# generic_micro_1.net
KiCad netlist of a schematic drawn in EAGLE
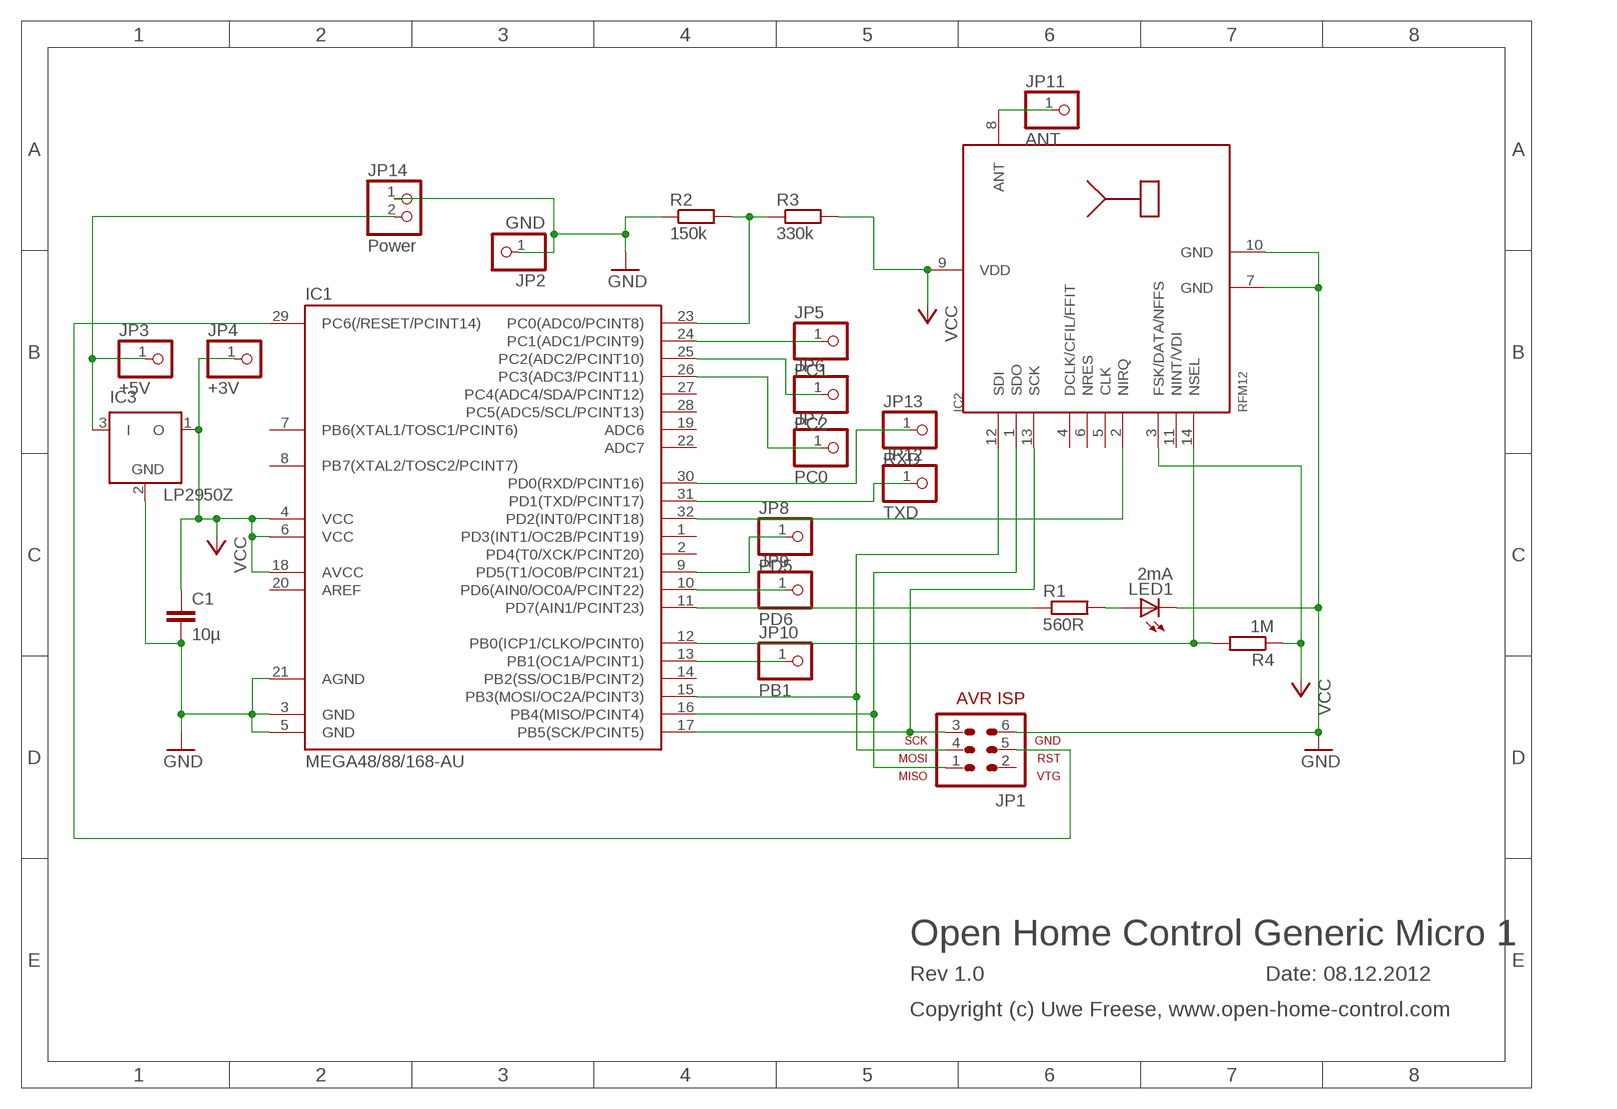
[diagram p0: schematic, sheet 1]

(export (version "E")
  (design (tool "Eeschema 10.0.6"))
  (components
    (comp (ref "C1")
      (value "10µ")
      (footprint "eagle-import:C0805")
      (libsource (lib "eagle-import") (part "C-EUC0805"))
    )
    (comp (ref "IC1")
      (value "MEGA48/88/168-AU")
      (footprint "eagle-import:TQFP32-08")
      (libsource (lib "eagle-import") (part "MEGA48/88/168-AU"))
    )
    (comp (ref "IC2")
      (value "RFM12")
      (footprint "eagle-import:RFM")
      (libsource (lib "eagle-import") (part "RFM12"))
    )
    (comp (ref "IC3")
      (value "LP2950Z")
      (footprint "eagle-import:TO92")
      (libsource (lib "eagle-import") (part "LP2950Z"))
    )
    (comp (ref "JP1")
      (value "AVR-ISP-6")
      (footprint "eagle-import:AVR-ISP-6")
      (libsource (lib "eagle-import") (part "AVR-ISP-6"))
    )
    (comp (ref "JP2")
      (value "GND")
      (footprint "eagle-import:1X01")
      (libsource (lib "eagle-import") (part "PINHD-1X1"))
    )
    (comp (ref "JP3")
      (value "+5V")
      (footprint "eagle-import:1X01")
      (libsource (lib "eagle-import") (part "PINHD-1X1"))
    )
    (comp (ref "JP4")
      (value "+3V")
      (footprint "eagle-import:1X01")
      (libsource (lib "eagle-import") (part "PINHD-1X1"))
    )
    (comp (ref "JP5")
      (value "PC1")
      (footprint "eagle-import:1X01")
      (libsource (lib "eagle-import") (part "PINHD-1X1"))
    )
    (comp (ref "JP6")
      (value "PC2")
      (footprint "eagle-import:1X01")
      (libsource (lib "eagle-import") (part "PINHD-1X1"))
    )
    (comp (ref "JP7")
      (value "PC0")
      (footprint "eagle-import:1X01")
      (libsource (lib "eagle-import") (part "PINHD-1X1"))
    )
    (comp (ref "JP8")
      (value "PD5")
      (footprint "eagle-import:1X01")
      (libsource (lib "eagle-import") (part "PINHD-1X1"))
    )
    (comp (ref "JP9")
      (value "PD6")
      (footprint "eagle-import:1X01")
      (libsource (lib "eagle-import") (part "PINHD-1X1"))
    )
    (comp (ref "JP10")
      (value "PB1")
      (footprint "eagle-import:1X01")
      (libsource (lib "eagle-import") (part "PINHD-1X1"))
    )
    (comp (ref "JP11")
      (value "ANT")
      (footprint "eagle-import:1X01")
      (libsource (lib "eagle-import") (part "PINHD-1X1"))
    )
    (comp (ref "JP12")
      (value "TXD")
      (footprint "eagle-import:1X01")
      (libsource (lib "eagle-import") (part "PINHD-1X1"))
    )
    (comp (ref "JP13")
      (value "RXD")
      (footprint "eagle-import:1X01")
      (libsource (lib "eagle-import") (part "PINHD-1X1"))
    )
    (comp (ref "JP14")
      (value "Power")
      (footprint "eagle-import:1X02")
      (libsource (lib "eagle-import") (part "PINHD-1X2"))
    )
    (comp (ref "LED1")
      (value "2mA")
      (footprint "eagle-import:LED3MM")
      (libsource (lib "eagle-import") (part "LED3MM"))
    )
    (comp (ref "R1")
      (value "560R")
      (footprint "eagle-import:R0603")
      (libsource (lib "eagle-import") (part "R-EU_R0603"))
    )
    (comp (ref "R2")
      (value "150k")
      (footprint "eagle-import:R0603")
      (libsource (lib "eagle-import") (part "R-EU_R0603"))
    )
    (comp (ref "R3")
      (value "330k")
      (footprint "eagle-import:R0603")
      (libsource (lib "eagle-import") (part "R-EU_R0603"))
    )
    (comp (ref "R4")
      (value "1M")
      (footprint "eagle-import:R0603")
      (libsource (lib "eagle-import") (part "R-EU_R0603"))
    )
  )
  (nets
    (net (code "1") (name "GND") (class "Default")
      (node (ref "C1") (pin "2") (pinfunction "2_2") (pintype "passive"))
      (node (ref "IC1") (pin "21") (pinfunction "AGND_21") (pintype "power_in"))
      (node (ref "IC1") (pin "3") (pinfunction "GND_3") (pintype "power_in"))
      (node (ref "IC1") (pin "5") (pinfunction "GND_5") (pintype "power_in"))
      (node (ref "IC2") (pin "10") (pinfunction "GND_10") (pintype "power_in"))
      (node (ref "IC2") (pin "7") (pinfunction "GND_7") (pintype "power_in"))
      (node (ref "IC3") (pin "2") (pinfunction "GND_2") (pintype "power_in"))
      (node (ref "JP1") (pin "6") (pinfunction "6_6") (pintype "passive"))
      (node (ref "JP14") (pin "1") (pinfunction "1_1") (pintype "passive"))
      (node (ref "JP2") (pin "1") (pinfunction "1_1") (pintype "passive"))
      (node (ref "LED1") (pin "K") (pinfunction "C_K") (pintype "passive"))
      (node (ref "R2") (pin "1") (pinfunction "1_1") (pintype "passive"))
    )
    (net (code "2") (name "Net-(IC1-PB0(ICP1{slash}CLKO{slash}PCINT0))") (class "Default")
      (node (ref "IC1") (pin "12") (pinfunction "PB0(ICP1/CLKO/PCINT0)_12") (pintype "bidirectional"))
      (node (ref "IC2") (pin "14") (pinfunction "NSEL_14") (pintype "bidirectional"))
      (node (ref "R4") (pin "2") (pinfunction "2_2") (pintype "passive"))
    )
    (net (code "3") (name "Net-(IC1-PB1(OC1A{slash}PCINT1))") (class "Default")
      (node (ref "IC1") (pin "13") (pinfunction "PB1(OC1A/PCINT1)_13") (pintype "bidirectional"))
      (node (ref "JP10") (pin "1") (pinfunction "1_1") (pintype "passive"))
    )
    (net (code "4") (name "Net-(IC1-PB3(MOSI{slash}OC2A{slash}PCINT3))") (class "Default")
      (node (ref "IC1") (pin "15") (pinfunction "PB3(MOSI/OC2A/PCINT3)_15") (pintype "bidirectional"))
      (node (ref "IC2") (pin "12") (pinfunction "SDI_12") (pintype "bidirectional"))
      (node (ref "JP1") (pin "4") (pinfunction "4_4") (pintype "passive"))
    )
    (net (code "5") (name "Net-(IC1-PB4(MISO{slash}PCINT4))") (class "Default")
      (node (ref "IC1") (pin "16") (pinfunction "PB4(MISO/PCINT4)_16") (pintype "bidirectional"))
      (node (ref "IC2") (pin "1") (pinfunction "SDO_1") (pintype "bidirectional"))
      (node (ref "JP1") (pin "1") (pinfunction "1_1") (pintype "passive"))
    )
    (net (code "6") (name "Net-(IC1-PB5(SCK{slash}PCINT5))") (class "Default")
      (node (ref "IC1") (pin "17") (pinfunction "PB5(SCK/PCINT5)_17") (pintype "bidirectional"))
      (node (ref "IC2") (pin "13") (pinfunction "SCK_13") (pintype "bidirectional"))
      (node (ref "JP1") (pin "3") (pinfunction "3_3") (pintype "passive"))
    )
    (net (code "7") (name "Net-(IC1-PC0(ADC0{slash}PCINT8))") (class "Default")
      (node (ref "IC1") (pin "23") (pinfunction "PC0(ADC0/PCINT8)_23") (pintype "bidirectional"))
      (node (ref "R2") (pin "2") (pinfunction "2_2") (pintype "passive"))
      (node (ref "R3") (pin "1") (pinfunction "1_1") (pintype "passive"))
    )
    (net (code "8") (name "Net-(IC1-PC1(ADC1{slash}PCINT9))") (class "Default")
      (node (ref "IC1") (pin "24") (pinfunction "PC1(ADC1/PCINT9)_24") (pintype "bidirectional"))
      (node (ref "JP5") (pin "1") (pinfunction "1_1") (pintype "passive"))
    )
    (net (code "9") (name "Net-(IC1-PC2(ADC2{slash}PCINT10))") (class "Default")
      (node (ref "IC1") (pin "25") (pinfunction "PC2(ADC2/PCINT10)_25") (pintype "bidirectional"))
      (node (ref "JP6") (pin "1") (pinfunction "1_1") (pintype "passive"))
    )
    (net (code "10") (name "Net-(IC1-PC3(ADC3{slash}PCINT11))") (class "Default")
      (node (ref "IC1") (pin "26") (pinfunction "PC3(ADC3/PCINT11)_26") (pintype "bidirectional"))
      (node (ref "JP7") (pin "1") (pinfunction "1_1") (pintype "passive"))
    )
    (net (code "11") (name "Net-(IC1-PC6({slash}RESET{slash}PCINT14))") (class "Default")
      (node (ref "IC1") (pin "29") (pinfunction "PC6(/RESET/PCINT14)_29") (pintype "bidirectional"))
      (node (ref "JP1") (pin "5") (pinfunction "5_5") (pintype "passive"))
    )
    (net (code "12") (name "Net-(IC1-PD0(RXD{slash}PCINT16))") (class "Default")
      (node (ref "IC1") (pin "30") (pinfunction "PD0(RXD/PCINT16)_30") (pintype "bidirectional"))
      (node (ref "JP13") (pin "1") (pinfunction "1_1") (pintype "passive"))
    )
    (net (code "13") (name "Net-(IC1-PD1(TXD{slash}PCINT17))") (class "Default")
      (node (ref "IC1") (pin "31") (pinfunction "PD1(TXD/PCINT17)_31") (pintype "bidirectional"))
      (node (ref "JP12") (pin "1") (pinfunction "1_1") (pintype "passive"))
    )
    (net (code "14") (name "Net-(IC1-PD2(INT0{slash}PCINT18))") (class "Default")
      (node (ref "IC1") (pin "32") (pinfunction "PD2(INT0/PCINT18)_32") (pintype "bidirectional"))
      (node (ref "IC2") (pin "2") (pinfunction "NIRQ_2") (pintype "bidirectional"))
    )
    (net (code "15") (name "Net-(IC1-PD5(T1{slash}OC0B{slash}PCINT21))") (class "Default")
      (node (ref "IC1") (pin "9") (pinfunction "PD5(T1/OC0B/PCINT21)_9") (pintype "bidirectional"))
      (node (ref "JP8") (pin "1") (pinfunction "1_1") (pintype "passive"))
    )
    (net (code "16") (name "Net-(IC1-PD6(AIN0{slash}OC0A{slash}PCINT22))") (class "Default")
      (node (ref "IC1") (pin "10") (pinfunction "PD6(AIN0/OC0A/PCINT22)_10") (pintype "bidirectional"))
      (node (ref "JP9") (pin "1") (pinfunction "1_1") (pintype "passive"))
    )
    (net (code "17") (name "Net-(IC1-PD7(AIN1{slash}PCINT23))") (class "Default")
      (node (ref "IC1") (pin "11") (pinfunction "PD7(AIN1/PCINT23)_11") (pintype "bidirectional"))
      (node (ref "R1") (pin "1") (pinfunction "1_1") (pintype "passive"))
    )
    (net (code "18") (name "Net-(IC2-ANT)") (class "Default")
      (node (ref "IC2") (pin "8") (pinfunction "ANT_8") (pintype "output"))
      (node (ref "JP11") (pin "1") (pinfunction "1_1") (pintype "passive"))
    )
    (net (code "19") (name "Net-(IC3-I)") (class "Default")
      (node (ref "IC3") (pin "3") (pinfunction "I_3") (pintype "input"))
      (node (ref "JP14") (pin "2") (pinfunction "2_2") (pintype "passive"))
      (node (ref "JP3") (pin "1") (pinfunction "1_1") (pintype "passive"))
    )
    (net (code "20") (name "Net-(LED1-PadA)") (class "Default")
      (node (ref "LED1") (pin "A") (pinfunction "A_A") (pintype "passive"))
      (node (ref "R1") (pin "2") (pinfunction "2_2") (pintype "passive"))
    )
    (net (code "21") (name "VCC") (class "Default")
      (node (ref "C1") (pin "1") (pinfunction "1_1") (pintype "passive"))
      (node (ref "IC1") (pin "18") (pinfunction "AVCC_18") (pintype "passive"))
      (node (ref "IC1") (pin "4") (pinfunction "VCC_4") (pintype "power_in"))
      (node (ref "IC1") (pin "6") (pinfunction "VCC_6") (pintype "power_in"))
      (node (ref "IC2") (pin "3") (pinfunction "FSK/DATA/NFFS_3") (pintype "bidirectional"))
      (node (ref "IC2") (pin "9") (pinfunction "VDD_9") (pintype "power_in"))
      (node (ref "IC3") (pin "1") (pinfunction "O_1") (pintype "input"))
      (node (ref "JP4") (pin "1") (pinfunction "1_1") (pintype "passive"))
      (node (ref "R3") (pin "2") (pinfunction "2_2") (pintype "passive"))
      (node (ref "R4") (pin "1") (pinfunction "1_1") (pintype "passive"))
    )
    (net (code "22") (name "unconnected-(IC1-ADC6-Pad19)") (class "Default")
      (node (ref "IC1") (pin "19") (pinfunction "ADC6_19") (pintype "passive"))
    )
    (net (code "23") (name "unconnected-(IC1-ADC7-Pad22)") (class "Default")
      (node (ref "IC1") (pin "22") (pinfunction "ADC7_22") (pintype "passive"))
    )
    (net (code "24") (name "unconnected-(IC1-AREF-Pad20)") (class "Default")
      (node (ref "IC1") (pin "20") (pinfunction "AREF_20") (pintype "passive"))
    )
    (net (code "25") (name "unconnected-(IC1-PB2(SS{slash}OC1B{slash}PCINT2)-Pad14)") (class "Default")
      (node (ref "IC1") (pin "14") (pinfunction "PB2(SS/OC1B/PCINT2)_14") (pintype "bidirectional"))
    )
    (net (code "26") (name "unconnected-(IC1-PB6(XTAL1{slash}TOSC1{slash}PCINT6)-Pad7)") (class "Default")
      (node (ref "IC1") (pin "7") (pinfunction "PB6(XTAL1/TOSC1/PCINT6)_7") (pintype "bidirectional"))
    )
    (net (code "27") (name "unconnected-(IC1-PB7(XTAL2{slash}TOSC2{slash}PCINT7)-Pad8)") (class "Default")
      (node (ref "IC1") (pin "8") (pinfunction "PB7(XTAL2/TOSC2/PCINT7)_8") (pintype "bidirectional"))
    )
    (net (code "28") (name "unconnected-(IC1-PC4(ADC4{slash}SDA{slash}PCINT12)-Pad27)") (class "Default")
      (node (ref "IC1") (pin "27") (pinfunction "PC4(ADC4/SDA/PCINT12)_27") (pintype "bidirectional"))
    )
    (net (code "29") (name "unconnected-(IC1-PC5(ADC5{slash}SCL{slash}PCINT13)-Pad28)") (class "Default")
      (node (ref "IC1") (pin "28") (pinfunction "PC5(ADC5/SCL/PCINT13)_28") (pintype "bidirectional"))
    )
    (net (code "30") (name "unconnected-(IC1-PD3(INT1{slash}OC2B{slash}PCINT19)-Pad1)") (class "Default")
      (node (ref "IC1") (pin "1") (pinfunction "PD3(INT1/OC2B/PCINT19)_1") (pintype "bidirectional"))
    )
    (net (code "31") (name "unconnected-(IC1-PD4(T0{slash}XCK{slash}PCINT20)-Pad2)") (class "Default")
      (node (ref "IC1") (pin "2") (pinfunction "PD4(T0/XCK/PCINT20)_2") (pintype "bidirectional"))
    )
    (net (code "32") (name "unconnected-(IC2-CLK-Pad5)") (class "Default")
      (node (ref "IC2") (pin "5") (pinfunction "CLK_5") (pintype "bidirectional"))
    )
    (net (code "33") (name "unconnected-(IC2-DCLK{slash}CFIL{slash}FFIT-Pad4)") (class "Default")
      (node (ref "IC2") (pin "4") (pinfunction "DCLK/CFIL/FFIT_4") (pintype "bidirectional"))
    )
    (net (code "34") (name "unconnected-(IC2-NINT{slash}VDI-Pad11)") (class "Default")
      (node (ref "IC2") (pin "11") (pinfunction "NINT/VDI_11") (pintype "bidirectional"))
    )
    (net (code "35") (name "unconnected-(IC2-NRES-Pad6)") (class "Default")
      (node (ref "IC2") (pin "6") (pinfunction "NRES_6") (pintype "bidirectional"))
    )
    (net (code "36") (name "unconnected-(JP1-Pad2)") (class "Default")
      (node (ref "JP1") (pin "2") (pinfunction "2_2") (pintype "passive"))
    )
  )
)
